# gpio_pcal9535a_expander.net
KiCad netlist of a schematic drawn in Altium Designer
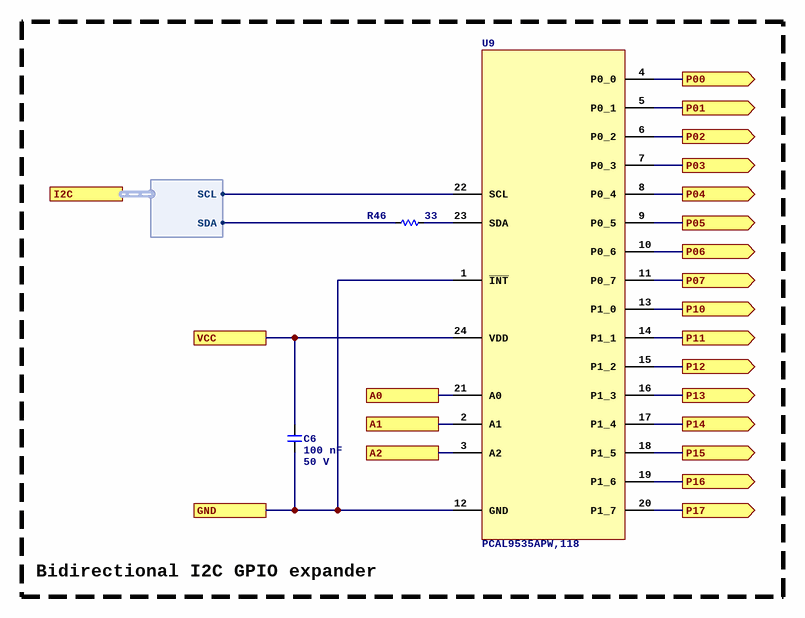
[diagram p0: gpio_pcal9535a_expander.SchDoc]

(export (version "E")
  (design (tool "Eeschema 10.0.6"))
  (components
    (comp (ref "C6")
      (value "CL05B104KB54PNC")
      (footprint "C0402")
      (fields
        (field (name "CAPACITANCE") "100 nF")
        (field (name "MANUFACTURER") "Samsung Electro-Mechanics")
        (field (name "VOLTAGE RATING") "50 V")
      )
      (libsource (lib "database") (part "__template_cap"))
    )
    (comp (ref "R46")
      (value "33")
      (footprint "R0402")
      (fields
        (field (name "TOLERANCE") "1%")
        (field (name "MANUFACTURER PART NUMBER") "CRCW040233R0FKED")
        (field (name "MANUFACTURER") "Vishay Intertech")
      )
      (libsource (lib "database") (part "__template_resistor"))
    )
    (comp (ref "U9")
      (value "PCAL9535APW,118")
      (footprint "24TSSOP65")
      (description "16-bit I2C/SMBus I/O expander, 400 kHz, with interrupt and Agile I/O, TSSOP-24")
      (fields (field (name "MANUFACTURER") "NXP Semiconductors"))
      (libsource (lib "database") (part "PCAL9535APW,118"))
    )
  )
  (nets
    (net (code "2") (name "/A0") (class "Default")
      (node (ref "U9") (pin "21") (pinfunction "A0_21") (pintype "passive"))
    )
    (net (code "3") (name "/A1") (class "Default")
      (node (ref "U9") (pin "2") (pinfunction "A1_2") (pintype "passive"))
    )
    (net (code "4") (name "/A2") (class "Default")
      (node (ref "U9") (pin "3") (pinfunction "A2_3") (pintype "passive"))
    )
    (net (code "5") (name "/GND") (class "Default")
      (node (ref "C6") (pin "2") (pintype "passive"))
      (node (ref "U9") (pin "1") (pinfunction "~{INT}_1") (pintype "passive"))
      (node (ref "U9") (pin "12") (pinfunction "GND_12") (pintype "passive"))
    )
    (net (code "6") (name "/P00") (class "Default")
      (node (ref "U9") (pin "4") (pinfunction "P0_0_4") (pintype "passive"))
    )
    (net (code "7") (name "/P01") (class "Default")
      (node (ref "U9") (pin "5") (pinfunction "P0_1_5") (pintype "passive"))
    )
    (net (code "8") (name "/P02") (class "Default")
      (node (ref "U9") (pin "6") (pinfunction "P0_2_6") (pintype "passive"))
    )
    (net (code "9") (name "/P03") (class "Default")
      (node (ref "U9") (pin "7") (pinfunction "P0_3_7") (pintype "passive"))
    )
    (net (code "10") (name "/P04") (class "Default")
      (node (ref "U9") (pin "8") (pinfunction "P0_4_8") (pintype "passive"))
    )
    (net (code "11") (name "/P05") (class "Default")
      (node (ref "U9") (pin "9") (pinfunction "P0_5_9") (pintype "passive"))
    )
    (net (code "12") (name "/P06") (class "Default")
      (node (ref "U9") (pin "10") (pinfunction "P0_6_10") (pintype "passive"))
    )
    (net (code "13") (name "/P07") (class "Default")
      (node (ref "U9") (pin "11") (pinfunction "P0_7_11") (pintype "passive"))
    )
    (net (code "14") (name "/P10") (class "Default")
      (node (ref "U9") (pin "13") (pinfunction "P1_0_13") (pintype "passive"))
    )
    (net (code "15") (name "/P11") (class "Default")
      (node (ref "U9") (pin "14") (pinfunction "P1_1_14") (pintype "passive"))
    )
    (net (code "16") (name "/P12") (class "Default")
      (node (ref "U9") (pin "15") (pinfunction "P1_2_15") (pintype "passive"))
    )
    (net (code "17") (name "/P13") (class "Default")
      (node (ref "U9") (pin "16") (pinfunction "P1_3_16") (pintype "passive"))
    )
    (net (code "18") (name "/P14") (class "Default")
      (node (ref "U9") (pin "17") (pinfunction "P1_4_17") (pintype "passive"))
    )
    (net (code "19") (name "/P15") (class "Default")
      (node (ref "U9") (pin "18") (pinfunction "P1_5_18") (pintype "passive"))
    )
    (net (code "20") (name "/P16") (class "Default")
      (node (ref "U9") (pin "19") (pinfunction "P1_6_19") (pintype "passive"))
    )
    (net (code "21") (name "/P17") (class "Default")
      (node (ref "U9") (pin "20") (pinfunction "P1_7_20") (pintype "passive"))
    )
    (net (code "22") (name "/SCL") (class "Default")
      (node (ref "U9") (pin "22") (pinfunction "SCL_22") (pintype "passive"))
    )
    (net (code "23") (name "/SDA") (class "Default") (node (ref "R46") (pin "2") (pintype "passive")))
    (net (code "24") (name "/VCC") (class "Default")
      (node (ref "C6") (pin "1") (pintype "passive"))
      (node (ref "U9") (pin "24") (pinfunction "VDD_24") (pintype "passive"))
    )
    (net (code "26") (name "Net-(U9-SDA)") (class "Default")
      (node (ref "R46") (pin "1") (pintype "passive"))
      (node (ref "U9") (pin "23") (pinfunction "SDA_23") (pintype "passive"))
    )
  )
)
